# HWCR.net
KiCad netlist of a schematic drawn in EAGLE
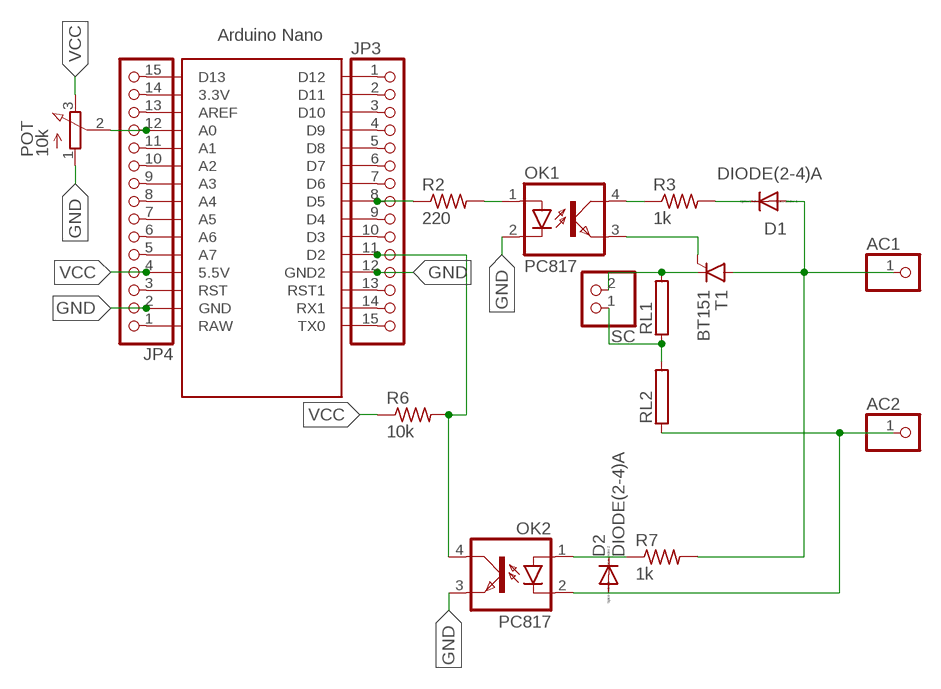
[diagram p0: schematic, sheet 1]

(export (version "E")
  (design (tool "Eeschema 10.0.6"))
  (components
    (comp (ref "AC1")
      (value "PINHD-1X1")
      (footprint "eagle-import:1X01")
      (libsource (lib "eagle-import") (part "PINHD-1X1"))
    )
    (comp (ref "AC2")
      (value "PINHD-1X1")
      (footprint "eagle-import:1X01")
      (libsource (lib "eagle-import") (part "PINHD-1X1"))
    )
    (comp (ref "D1")
      (value "DIODE(2-4)A")
      (footprint "eagle-import:DO35-10")
      (libsource (lib "eagle-import") (part "DIODE(2-4)A"))
    )
    (comp (ref "D2")
      (value "DIODE(2-4)A")
      (footprint "eagle-import:DO35-10")
      (libsource (lib "eagle-import") (part "DIODE(2-4)A"))
    )
    (comp (ref "JP3")
      (value "PINHD-1X15")
      (footprint "eagle-import:1X15")
      (libsource (lib "eagle-import") (part "PINHD-1X15"))
    )
    (comp (ref "JP4")
      (value "PINHD-1X15")
      (footprint "eagle-import:1X15")
      (libsource (lib "eagle-import") (part "PINHD-1X15"))
    )
    (comp (ref "OK1")
      (value "PC817")
      (footprint "eagle-import:DIL04")
      (fields (field (name "MPN") "PC817X4J000F"))
      (libsource (lib "eagle-import") (part "PC817"))
    )
    (comp (ref "OK2")
      (value "PC817")
      (footprint "eagle-import:DIL04")
      (fields (field (name "MPN") "PC817X4J000F"))
      (libsource (lib "eagle-import") (part "PC817"))
    )
    (comp (ref "POT")
      (value "10k")
      (footprint "eagle-import:3RP_1610N")
      (libsource (lib "eagle-import") (part "POTENTIOMETER"))
    )
    (comp (ref "R2")
      (value "220")
      (footprint "eagle-import:0207_10")
      (libsource (lib "eagle-import") (part "R-US_0207/10"))
    )
    (comp (ref "R3")
      (value "1k")
      (footprint "eagle-import:0207_10")
      (libsource (lib "eagle-import") (part "R-US_0207/10"))
    )
    (comp (ref "R6")
      (value "10k")
      (footprint "eagle-import:0207_10")
      (libsource (lib "eagle-import") (part "R-US_0207/10"))
    )
    (comp (ref "R7")
      (value "1k")
      (footprint "eagle-import:0207_10")
      (libsource (lib "eagle-import") (part "R-US_0207/10"))
    )
    (comp (ref "RL1")
      (value "RKP296")
      (footprint "eagle-import:KP296")
      (libsource (lib "eagle-import") (part "RKP296"))
    )
    (comp (ref "RL2")
      (value "RKP296")
      (footprint "eagle-import:KP296")
      (libsource (lib "eagle-import") (part "RKP296"))
    )
    (comp (ref "SC")
      (value "PINHD-1X2")
      (footprint "eagle-import:1X02")
      (libsource (lib "eagle-import") (part "PINHD-1X2"))
    )
    (comp (ref "T1")
      (value "BT151")
      (footprint "eagle-import:TO220CL")
      (libsource (lib "eagle-import") (part "BT151"))
    )
    (comp (ref "U$1")
      (value "ARDUINO_NANO")
      (footprint "eagle-import:NANO")
      (libsource (lib "eagle-import") (part "ARDUINO_NANO"))
    )
  )
  (nets
    (net (code "1") (name "GND") (class "Default")
      (node (ref "JP3") (pin "12") (pinfunction "12_12") (pintype "passive"))
      (node (ref "JP4") (pin "2") (pinfunction "2_2") (pintype "passive"))
      (node (ref "OK1") (pin "2") (pinfunction "C_2") (pintype "passive"))
      (node (ref "OK2") (pin "3") (pinfunction "EMIT_3") (pintype "passive"))
      (node (ref "POT") (pin "1") (pinfunction "A_1") (pintype "passive"))
      (node (ref "U$1") (pin "GND") (pinfunction "GND_GND") (pintype "bidirectional"))
      (node (ref "U$1") (pin "GND1") (pinfunction "GND2_GND1") (pintype "bidirectional"))
    )
    (net (code "2") (name "Net-(AC1-Pad1)") (class "Default")
      (node (ref "AC1") (pin "1") (pinfunction "1_1") (pintype "passive"))
      (node (ref "D1") (pin "A") (pinfunction "A_A") (pintype "passive"))
      (node (ref "R7") (pin "2") (pinfunction "2_2") (pintype "passive"))
      (node (ref "T1") (pin "A") (pinfunction "A_A") (pintype "passive"))
    )
    (net (code "3") (name "Net-(D1-PadC)") (class "Default")
      (node (ref "D1") (pin "C") (pinfunction "C_C") (pintype "passive"))
      (node (ref "R3") (pin "2") (pinfunction "2_2") (pintype "passive"))
    )
    (net (code "4") (name "Net-(JP3-Pad1)") (class "Default")
      (node (ref "JP3") (pin "1") (pinfunction "1_1") (pintype "passive"))
      (node (ref "U$1") (pin "D12") (pinfunction "D12_D12") (pintype "bidirectional"))
    )
    (net (code "5") (name "Net-(JP3-Pad2)") (class "Default")
      (node (ref "JP3") (pin "2") (pinfunction "2_2") (pintype "passive"))
      (node (ref "U$1") (pin "D11") (pinfunction "D11_D11") (pintype "bidirectional"))
    )
    (net (code "6") (name "Net-(JP3-Pad3)") (class "Default")
      (node (ref "JP3") (pin "3") (pinfunction "3_3") (pintype "passive"))
      (node (ref "U$1") (pin "D10") (pinfunction "D10_D10") (pintype "bidirectional"))
    )
    (net (code "7") (name "Net-(JP3-Pad4)") (class "Default")
      (node (ref "JP3") (pin "4") (pinfunction "4_4") (pintype "passive"))
      (node (ref "U$1") (pin "D9") (pinfunction "D9_D9") (pintype "bidirectional"))
    )
    (net (code "8") (name "Net-(JP3-Pad5)") (class "Default")
      (node (ref "JP3") (pin "5") (pinfunction "5_5") (pintype "passive"))
      (node (ref "U$1") (pin "D8") (pinfunction "D8_D8") (pintype "bidirectional"))
    )
    (net (code "9") (name "Net-(JP3-Pad6)") (class "Default")
      (node (ref "JP3") (pin "6") (pinfunction "6_6") (pintype "passive"))
      (node (ref "U$1") (pin "D7") (pinfunction "D7_D7") (pintype "bidirectional"))
    )
    (net (code "10") (name "Net-(JP3-Pad7)") (class "Default")
      (node (ref "JP3") (pin "7") (pinfunction "7_7") (pintype "passive"))
      (node (ref "U$1") (pin "D6") (pinfunction "D6_D6") (pintype "bidirectional"))
    )
    (net (code "11") (name "Net-(JP3-Pad8)") (class "Default")
      (node (ref "JP3") (pin "8") (pinfunction "8_8") (pintype "passive"))
      (node (ref "R2") (pin "1") (pinfunction "1_1") (pintype "passive"))
      (node (ref "U$1") (pin "D5") (pinfunction "D5_D5") (pintype "bidirectional"))
    )
    (net (code "12") (name "Net-(JP3-Pad9)") (class "Default")
      (node (ref "JP3") (pin "9") (pinfunction "9_9") (pintype "passive"))
      (node (ref "U$1") (pin "D4") (pinfunction "D4_D4") (pintype "bidirectional"))
    )
    (net (code "13") (name "Net-(JP3-Pad10)") (class "Default")
      (node (ref "JP3") (pin "10") (pinfunction "10_10") (pintype "passive"))
      (node (ref "U$1") (pin "D3") (pinfunction "D3_D3") (pintype "bidirectional"))
    )
    (net (code "14") (name "Net-(JP3-Pad13)") (class "Default")
      (node (ref "JP3") (pin "13") (pinfunction "13_13") (pintype "passive"))
      (node (ref "U$1") (pin "RST1") (pinfunction "RST1_RST1") (pintype "bidirectional"))
    )
    (net (code "15") (name "Net-(JP3-Pad14)") (class "Default")
      (node (ref "JP3") (pin "14") (pinfunction "14_14") (pintype "passive"))
      (node (ref "U$1") (pin "RX1") (pinfunction "RX1_RX1") (pintype "bidirectional"))
    )
    (net (code "16") (name "Net-(JP3-Pad15)") (class "Default")
      (node (ref "JP3") (pin "15") (pinfunction "15_15") (pintype "passive"))
      (node (ref "U$1") (pin "TX0") (pinfunction "TX0_TX0") (pintype "bidirectional"))
    )
    (net (code "17") (name "Net-(JP4-Pad1)") (class "Default")
      (node (ref "JP4") (pin "1") (pinfunction "1_1") (pintype "passive"))
      (node (ref "U$1") (pin "RAW") (pinfunction "RAW_RAW") (pintype "bidirectional"))
    )
    (net (code "18") (name "Net-(JP4-Pad3)") (class "Default")
      (node (ref "JP4") (pin "3") (pinfunction "3_3") (pintype "passive"))
      (node (ref "U$1") (pin "RST") (pinfunction "RST_RST") (pintype "bidirectional"))
    )
    (net (code "19") (name "Net-(JP4-Pad5)") (class "Default")
      (node (ref "JP4") (pin "5") (pinfunction "5_5") (pintype "passive"))
      (node (ref "U$1") (pin "A7") (pinfunction "A7_A7") (pintype "bidirectional"))
    )
    (net (code "20") (name "Net-(JP4-Pad6)") (class "Default")
      (node (ref "JP4") (pin "6") (pinfunction "6_6") (pintype "passive"))
      (node (ref "U$1") (pin "A6") (pinfunction "A6_A6") (pintype "bidirectional"))
    )
    (net (code "21") (name "Net-(JP4-Pad7)") (class "Default")
      (node (ref "JP4") (pin "7") (pinfunction "7_7") (pintype "passive"))
      (node (ref "U$1") (pin "A5") (pinfunction "A5_A5") (pintype "bidirectional"))
    )
    (net (code "22") (name "Net-(JP4-Pad8)") (class "Default")
      (node (ref "JP4") (pin "8") (pinfunction "8_8") (pintype "passive"))
      (node (ref "U$1") (pin "A4") (pinfunction "A4_A4") (pintype "bidirectional"))
    )
    (net (code "23") (name "Net-(JP4-Pad9)") (class "Default")
      (node (ref "JP4") (pin "9") (pinfunction "9_9") (pintype "passive"))
      (node (ref "U$1") (pin "A3") (pinfunction "A3_A3") (pintype "bidirectional"))
    )
    (net (code "24") (name "Net-(JP4-Pad10)") (class "Default")
      (node (ref "JP4") (pin "10") (pinfunction "10_10") (pintype "passive"))
      (node (ref "U$1") (pin "A2") (pinfunction "A2_A2") (pintype "bidirectional"))
    )
    (net (code "25") (name "Net-(JP4-Pad11)") (class "Default")
      (node (ref "JP4") (pin "11") (pinfunction "11_11") (pintype "passive"))
      (node (ref "U$1") (pin "A1") (pinfunction "A1_A1") (pintype "bidirectional"))
    )
    (net (code "26") (name "Net-(JP4-Pad13)") (class "Default")
      (node (ref "JP4") (pin "13") (pinfunction "13_13") (pintype "passive"))
      (node (ref "U$1") (pin "AREF") (pinfunction "AREF_AREF") (pintype "bidirectional"))
    )
    (net (code "27") (name "Net-(JP4-Pad14)") (class "Default")
      (node (ref "JP4") (pin "14") (pinfunction "14_14") (pintype "passive"))
      (node (ref "U$1") (pin "3.3V") (pinfunction "3.3V_3.3V") (pintype "bidirectional"))
    )
    (net (code "28") (name "Net-(JP4-Pad15)") (class "Default")
      (node (ref "JP4") (pin "15") (pinfunction "15_15") (pintype "passive"))
      (node (ref "U$1") (pin "D13") (pinfunction "D13_D13") (pintype "bidirectional"))
    )
    (net (code "29") (name "Net-(OK1-A)") (class "Default")
      (node (ref "OK1") (pin "1") (pinfunction "A_1") (pintype "passive"))
      (node (ref "R2") (pin "2") (pinfunction "2_2") (pintype "passive"))
    )
    (net (code "30") (name "Net-(OK1-COL)") (class "Default")
      (node (ref "OK1") (pin "4") (pinfunction "COL_4") (pintype "passive"))
      (node (ref "R3") (pin "1") (pinfunction "1_1") (pintype "passive"))
    )
    (net (code "31") (name "Net-(OK1-EMIT)") (class "Default")
      (node (ref "OK1") (pin "3") (pinfunction "EMIT_3") (pintype "passive"))
      (node (ref "T1") (pin "G") (pinfunction "G_G") (pintype "passive"))
    )
    (net (code "32") (name "Net-(OK2-A)") (class "Default")
      (node (ref "D2") (pin "C") (pinfunction "C_C") (pintype "passive"))
      (node (ref "OK2") (pin "1") (pinfunction "A_1") (pintype "passive"))
      (node (ref "R7") (pin "1") (pinfunction "1_1") (pintype "passive"))
    )
    (net (code "33") (name "Net-(OK2-C)") (class "Default")
      (node (ref "AC2") (pin "1") (pinfunction "1_1") (pintype "passive"))
      (node (ref "D2") (pin "A") (pinfunction "A_A") (pintype "passive"))
      (node (ref "OK2") (pin "2") (pinfunction "C_2") (pintype "passive"))
      (node (ref "RL2") (pin "1") (pinfunction "1_1") (pintype "passive"))
    )
    (net (code "34") (name "Net-(OK2-COL)") (class "Default")
      (node (ref "JP3") (pin "11") (pinfunction "11_11") (pintype "passive"))
      (node (ref "OK2") (pin "4") (pinfunction "COL_4") (pintype "passive"))
      (node (ref "R6") (pin "2") (pinfunction "2_2") (pintype "passive"))
      (node (ref "U$1") (pin "D2") (pinfunction "D2_D2") (pintype "bidirectional"))
    )
    (net (code "35") (name "Net-(POT-S)") (class "Default")
      (node (ref "JP4") (pin "12") (pinfunction "12_12") (pintype "passive"))
      (node (ref "POT") (pin "2") (pinfunction "S_2") (pintype "passive"))
      (node (ref "U$1") (pin "A0") (pinfunction "A0_A0") (pintype "bidirectional"))
    )
    (net (code "36") (name "Net-(RL1-Pad1)") (class "Default")
      (node (ref "RL1") (pin "1") (pinfunction "1_1") (pintype "passive"))
      (node (ref "RL2") (pin "2") (pinfunction "2_2") (pintype "passive"))
      (node (ref "SC") (pin "1") (pinfunction "1_1") (pintype "passive"))
    )
    (net (code "37") (name "Net-(RL1-Pad2)") (class "Default")
      (node (ref "RL1") (pin "2") (pinfunction "2_2") (pintype "passive"))
      (node (ref "SC") (pin "2") (pinfunction "2_2") (pintype "passive"))
      (node (ref "T1") (pin "C") (pinfunction "C_C") (pintype "passive"))
    )
    (net (code "38") (name "VCC") (class "Default")
      (node (ref "JP4") (pin "4") (pinfunction "4_4") (pintype "passive"))
      (node (ref "POT") (pin "3") (pinfunction "E_3") (pintype "passive"))
      (node (ref "R6") (pin "1") (pinfunction "1_1") (pintype "passive"))
      (node (ref "U$1") (pin "5V") (pinfunction "5.5V_5V") (pintype "bidirectional"))
    )
  )
)
